# 0119-m328p.net
KiCad netlist of a schematic drawn in EAGLE
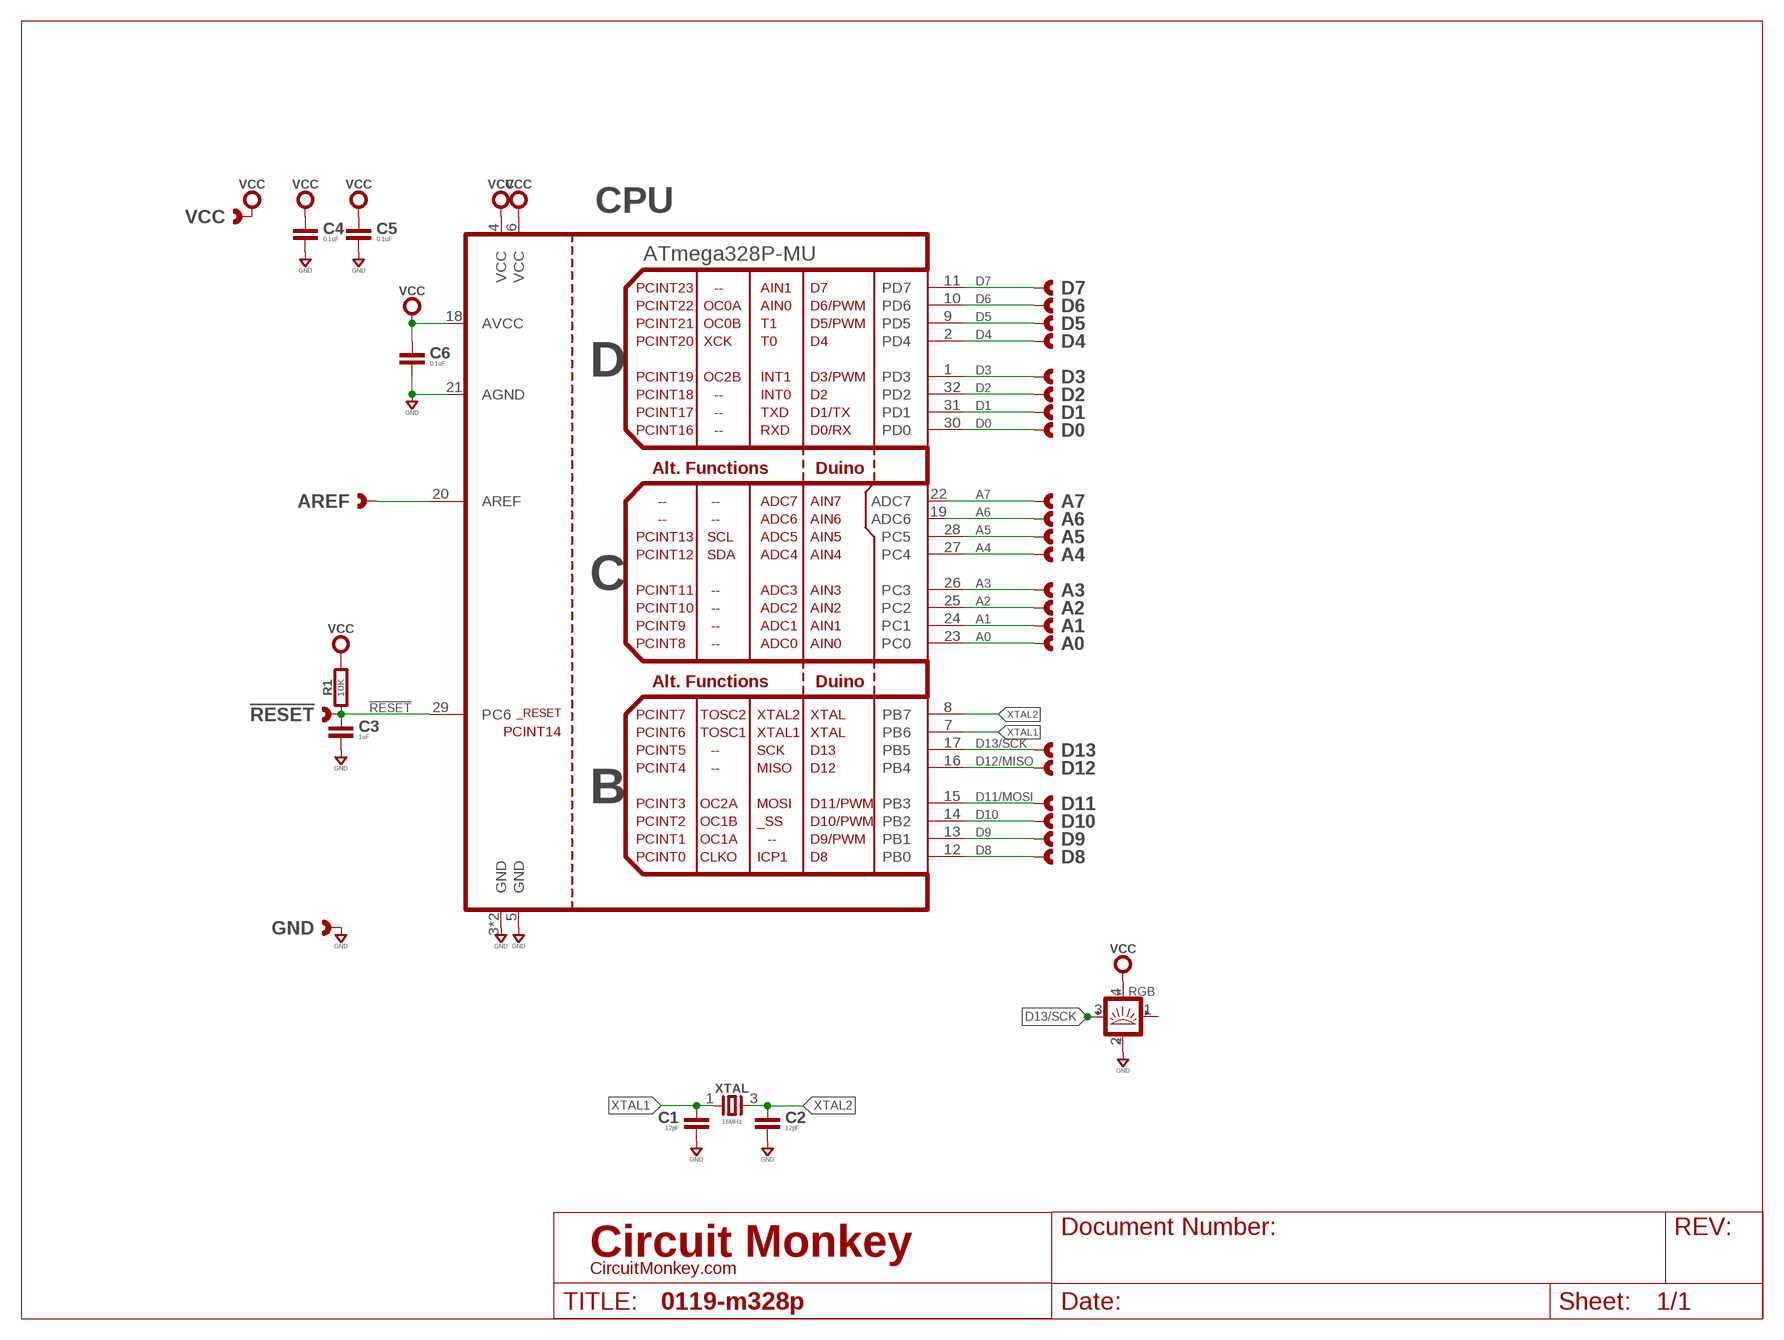
[diagram p0: schematic, sheet 1]

(export (version "E")
  (design (tool "Eeschema 10.0.6"))
  (components
    (comp (ref "!RESET")
      (value "CAST-01X12.00MM")
      (footprint "eagle-import:CAST01-2.00MM")
      (libsource (lib "eagle-import") (part "CAST-01X12.00MM"))
    )
    (comp (ref "A0")
      (value "CAST-01X12.00MM")
      (footprint "eagle-import:CAST01-2.00MM")
      (libsource (lib "eagle-import") (part "CAST-01X12.00MM"))
    )
    (comp (ref "A1")
      (value "CAST-01X12.00MM")
      (footprint "eagle-import:CAST01-2.00MM")
      (libsource (lib "eagle-import") (part "CAST-01X12.00MM"))
    )
    (comp (ref "A2")
      (value "CAST-01X12.00MM")
      (footprint "eagle-import:CAST01-2.00MM")
      (libsource (lib "eagle-import") (part "CAST-01X12.00MM"))
    )
    (comp (ref "A3")
      (value "CAST-01X12.00MM")
      (footprint "eagle-import:CAST01-2.00MM")
      (libsource (lib "eagle-import") (part "CAST-01X12.00MM"))
    )
    (comp (ref "A4")
      (value "CAST-01X12.00MM")
      (footprint "eagle-import:CAST01-2.00MM")
      (libsource (lib "eagle-import") (part "CAST-01X12.00MM"))
    )
    (comp (ref "A5")
      (value "CAST-01X12.00MM")
      (footprint "eagle-import:CAST01-2.00MM")
      (libsource (lib "eagle-import") (part "CAST-01X12.00MM"))
    )
    (comp (ref "A6")
      (value "CAST-01X12.00MM")
      (footprint "eagle-import:CAST01-2.00MM")
      (libsource (lib "eagle-import") (part "CAST-01X12.00MM"))
    )
    (comp (ref "A7")
      (value "CAST-01X12.00MM")
      (footprint "eagle-import:CAST01-2.00MM")
      (libsource (lib "eagle-import") (part "CAST-01X12.00MM"))
    )
    (comp (ref "AREF")
      (value "CAST-01X12.00MM")
      (footprint "eagle-import:CAST01-2.00MM")
      (libsource (lib "eagle-import") (part "CAST-01X12.00MM"))
    )
    (comp (ref "C1")
      (value "12pF")
      (footprint "eagle-import:0402-CAP")
      (libsource (lib "eagle-import") (part "CAPACITOR0402"))
    )
    (comp (ref "C2")
      (value "12pF")
      (footprint "eagle-import:0402-CAP")
      (libsource (lib "eagle-import") (part "CAPACITOR0402"))
    )
    (comp (ref "C3")
      (value "1uF")
      (footprint "eagle-import:0402-CAP")
      (libsource (lib "eagle-import") (part "CAPACITOR0402"))
    )
    (comp (ref "C4")
      (value "0.1uF")
      (footprint "eagle-import:0402-CAP")
      (libsource (lib "eagle-import") (part "CAPACITOR0402"))
    )
    (comp (ref "C5")
      (value "0.1uF")
      (footprint "eagle-import:0402-CAP")
      (libsource (lib "eagle-import") (part "CAPACITOR0402"))
    )
    (comp (ref "C6")
      (value "0.1uF")
      (footprint "eagle-import:0402-CAP")
      (libsource (lib "eagle-import") (part "CAPACITOR0402"))
    )
    (comp (ref "CPU")
      (value "ATmega328P-MU")
      (footprint "eagle-import:MLF32")
      (fields (field (name "MFR") "Atmel") (field (name "MPN") "atmega328p-mu"))
      (libsource (lib "eagle-import") (part "ATMEGA328MU"))
    )
    (comp (ref "D0")
      (value "CAST-01X12.00MM")
      (footprint "eagle-import:CAST01-2.00MM")
      (libsource (lib "eagle-import") (part "CAST-01X12.00MM"))
    )
    (comp (ref "D1")
      (value "CAST-01X12.00MM")
      (footprint "eagle-import:CAST01-2.00MM")
      (libsource (lib "eagle-import") (part "CAST-01X12.00MM"))
    )
    (comp (ref "D2")
      (value "CAST-01X12.00MM")
      (footprint "eagle-import:CAST01-2.00MM")
      (libsource (lib "eagle-import") (part "CAST-01X12.00MM"))
    )
    (comp (ref "D3")
      (value "CAST-01X12.00MM")
      (footprint "eagle-import:CAST01-2.00MM")
      (libsource (lib "eagle-import") (part "CAST-01X12.00MM"))
    )
    (comp (ref "D4")
      (value "CAST-01X12.00MM")
      (footprint "eagle-import:CAST01-2.00MM")
      (libsource (lib "eagle-import") (part "CAST-01X12.00MM"))
    )
    (comp (ref "D5")
      (value "CAST-01X12.00MM")
      (footprint "eagle-import:CAST01-2.00MM")
      (libsource (lib "eagle-import") (part "CAST-01X12.00MM"))
    )
    (comp (ref "D6")
      (value "CAST-01X12.00MM")
      (footprint "eagle-import:CAST01-2.00MM")
      (libsource (lib "eagle-import") (part "CAST-01X12.00MM"))
    )
    (comp (ref "D7")
      (value "CAST-01X12.00MM")
      (footprint "eagle-import:CAST01-2.00MM")
      (libsource (lib "eagle-import") (part "CAST-01X12.00MM"))
    )
    (comp (ref "D8")
      (value "CAST-01X12.00MM")
      (footprint "eagle-import:CAST01-2.00MM")
      (libsource (lib "eagle-import") (part "CAST-01X12.00MM"))
    )
    (comp (ref "D9")
      (value "CAST-01X12.00MM")
      (footprint "eagle-import:CAST01-2.00MM")
      (libsource (lib "eagle-import") (part "CAST-01X12.00MM"))
    )
    (comp (ref "D10")
      (value "CAST-01X12.00MM")
      (footprint "eagle-import:CAST01-2.00MM")
      (libsource (lib "eagle-import") (part "CAST-01X12.00MM"))
    )
    (comp (ref "D11")
      (value "CAST-01X12.00MM")
      (footprint "eagle-import:CAST01-2.00MM")
      (libsource (lib "eagle-import") (part "CAST-01X12.00MM"))
    )
    (comp (ref "D12")
      (value "CAST-01X12.00MM")
      (footprint "eagle-import:CAST01-2.00MM")
      (libsource (lib "eagle-import") (part "CAST-01X12.00MM"))
    )
    (comp (ref "D13")
      (value "CAST-01X12.00MM")
      (footprint "eagle-import:CAST01-2.00MM")
      (libsource (lib "eagle-import") (part "CAST-01X12.00MM"))
    )
    (comp (ref "GND")
      (value "CAST-01X12.00MM")
      (footprint "eagle-import:CAST01-2.00MM")
      (libsource (lib "eagle-import") (part "CAST-01X12.00MM"))
    )
    (comp (ref "R1")
      (value "10K")
      (footprint "eagle-import:0402-RES")
      (libsource (lib "eagle-import") (part "RESISTOR0402"))
    )
    (comp (ref "RGB")
      (value "SMART_LED2020")
      (footprint "eagle-import:SMD_2020")
      (libsource (lib "eagle-import") (part "SMART_LED2020"))
    )
    (comp (ref "VCC")
      (value "CAST-01X12.00MM")
      (footprint "eagle-import:CAST01-2.00MM")
      (libsource (lib "eagle-import") (part "CAST-01X12.00MM"))
    )
    (comp (ref "XTAL")
      (value "16MHz")
      (footprint "eagle-import:32X25")
      (fields (field (name "MF") "Epson") (field (name "MPN") "FA-238 16.0000MB-K3"))
      (libsource (lib "eagle-import") (part "2P3.2X2.5"))
    )
  )
  (nets
    (net (code "1") (name "/A0") (class "Default")
      (node (ref "A0") (pin "1") (pinfunction "1_1") (pintype "bidirectional"))
      (node (ref "A0") (pin "P$1") (pinfunction "1_P$1") (pintype "bidirectional"))
      (node (ref "A0") (pin "P$2") (pinfunction "1_P$2") (pintype "bidirectional"))
      (node (ref "CPU") (pin "23") (pinfunction "PC0_23") (pintype "bidirectional"))
    )
    (net (code "2") (name "/A1") (class "Default")
      (node (ref "A1") (pin "1") (pinfunction "1_1") (pintype "bidirectional"))
      (node (ref "A1") (pin "P$1") (pinfunction "1_P$1") (pintype "bidirectional"))
      (node (ref "A1") (pin "P$2") (pinfunction "1_P$2") (pintype "bidirectional"))
      (node (ref "CPU") (pin "24") (pinfunction "PC1_24") (pintype "bidirectional"))
    )
    (net (code "3") (name "/A2") (class "Default")
      (node (ref "A2") (pin "1") (pinfunction "1_1") (pintype "bidirectional"))
      (node (ref "A2") (pin "P$1") (pinfunction "1_P$1") (pintype "bidirectional"))
      (node (ref "A2") (pin "P$2") (pinfunction "1_P$2") (pintype "bidirectional"))
      (node (ref "CPU") (pin "25") (pinfunction "PC2_25") (pintype "bidirectional"))
    )
    (net (code "4") (name "/A3") (class "Default")
      (node (ref "A3") (pin "1") (pinfunction "1_1") (pintype "bidirectional"))
      (node (ref "A3") (pin "P$1") (pinfunction "1_P$1") (pintype "bidirectional"))
      (node (ref "A3") (pin "P$2") (pinfunction "1_P$2") (pintype "bidirectional"))
      (node (ref "CPU") (pin "26") (pinfunction "PC3_26") (pintype "bidirectional"))
    )
    (net (code "5") (name "/A4") (class "Default")
      (node (ref "A4") (pin "1") (pinfunction "1_1") (pintype "bidirectional"))
      (node (ref "A4") (pin "P$1") (pinfunction "1_P$1") (pintype "bidirectional"))
      (node (ref "A4") (pin "P$2") (pinfunction "1_P$2") (pintype "bidirectional"))
      (node (ref "CPU") (pin "27") (pinfunction "PC4_27") (pintype "bidirectional"))
    )
    (net (code "6") (name "/A5") (class "Default")
      (node (ref "A5") (pin "1") (pinfunction "1_1") (pintype "bidirectional"))
      (node (ref "A5") (pin "P$1") (pinfunction "1_P$1") (pintype "bidirectional"))
      (node (ref "A5") (pin "P$2") (pinfunction "1_P$2") (pintype "bidirectional"))
      (node (ref "CPU") (pin "28") (pinfunction "PC5_28") (pintype "bidirectional"))
    )
    (net (code "7") (name "/A6") (class "Default")
      (node (ref "A6") (pin "1") (pinfunction "1_1") (pintype "bidirectional"))
      (node (ref "A6") (pin "P$1") (pinfunction "1_P$1") (pintype "bidirectional"))
      (node (ref "A6") (pin "P$2") (pinfunction "1_P$2") (pintype "bidirectional"))
      (node (ref "CPU") (pin "19") (pinfunction "ADC6_19") (pintype "bidirectional"))
    )
    (net (code "8") (name "/A7") (class "Default")
      (node (ref "A7") (pin "1") (pinfunction "1_1") (pintype "bidirectional"))
      (node (ref "A7") (pin "P$1") (pinfunction "1_P$1") (pintype "bidirectional"))
      (node (ref "A7") (pin "P$2") (pinfunction "1_P$2") (pintype "bidirectional"))
      (node (ref "CPU") (pin "22") (pinfunction "ADC7_22") (pintype "bidirectional"))
    )
    (net (code "9") (name "/D0") (class "Default")
      (node (ref "CPU") (pin "30") (pinfunction "PD0_30") (pintype "bidirectional"))
      (node (ref "D0") (pin "1") (pinfunction "1_1") (pintype "bidirectional"))
      (node (ref "D0") (pin "P$1") (pinfunction "1_P$1") (pintype "bidirectional"))
      (node (ref "D0") (pin "P$2") (pinfunction "1_P$2") (pintype "bidirectional"))
    )
    (net (code "10") (name "/D1") (class "Default")
      (node (ref "CPU") (pin "31") (pinfunction "PD1_31") (pintype "bidirectional"))
      (node (ref "D1") (pin "1") (pinfunction "1_1") (pintype "bidirectional"))
      (node (ref "D1") (pin "P$1") (pinfunction "1_P$1") (pintype "bidirectional"))
      (node (ref "D1") (pin "P$2") (pinfunction "1_P$2") (pintype "bidirectional"))
    )
    (net (code "11") (name "/D2") (class "Default")
      (node (ref "CPU") (pin "32") (pinfunction "PD2_32") (pintype "bidirectional"))
      (node (ref "D2") (pin "1") (pinfunction "1_1") (pintype "bidirectional"))
      (node (ref "D2") (pin "P$1") (pinfunction "1_P$1") (pintype "bidirectional"))
      (node (ref "D2") (pin "P$2") (pinfunction "1_P$2") (pintype "bidirectional"))
    )
    (net (code "12") (name "/D3") (class "Default")
      (node (ref "CPU") (pin "1") (pinfunction "PD3_1") (pintype "bidirectional"))
      (node (ref "D3") (pin "1") (pinfunction "1_1") (pintype "bidirectional"))
      (node (ref "D3") (pin "P$1") (pinfunction "1_P$1") (pintype "bidirectional"))
      (node (ref "D3") (pin "P$2") (pinfunction "1_P$2") (pintype "bidirectional"))
    )
    (net (code "13") (name "/D4") (class "Default")
      (node (ref "CPU") (pin "2") (pinfunction "PD4_2") (pintype "bidirectional"))
      (node (ref "D4") (pin "1") (pinfunction "1_1") (pintype "bidirectional"))
      (node (ref "D4") (pin "P$1") (pinfunction "1_P$1") (pintype "bidirectional"))
      (node (ref "D4") (pin "P$2") (pinfunction "1_P$2") (pintype "bidirectional"))
    )
    (net (code "14") (name "/D5") (class "Default")
      (node (ref "CPU") (pin "9") (pinfunction "PD5_9") (pintype "bidirectional"))
      (node (ref "D5") (pin "1") (pinfunction "1_1") (pintype "bidirectional"))
      (node (ref "D5") (pin "P$1") (pinfunction "1_P$1") (pintype "bidirectional"))
      (node (ref "D5") (pin "P$2") (pinfunction "1_P$2") (pintype "bidirectional"))
    )
    (net (code "15") (name "/D6") (class "Default")
      (node (ref "CPU") (pin "10") (pinfunction "PD6_10") (pintype "bidirectional"))
      (node (ref "D6") (pin "1") (pinfunction "1_1") (pintype "bidirectional"))
      (node (ref "D6") (pin "P$1") (pinfunction "1_P$1") (pintype "bidirectional"))
      (node (ref "D6") (pin "P$2") (pinfunction "1_P$2") (pintype "bidirectional"))
    )
    (net (code "16") (name "/D7") (class "Default")
      (node (ref "CPU") (pin "11") (pinfunction "PD7_11") (pintype "bidirectional"))
      (node (ref "D7") (pin "1") (pinfunction "1_1") (pintype "bidirectional"))
      (node (ref "D7") (pin "P$1") (pinfunction "1_P$1") (pintype "bidirectional"))
      (node (ref "D7") (pin "P$2") (pinfunction "1_P$2") (pintype "bidirectional"))
    )
    (net (code "17") (name "/D8") (class "Default")
      (node (ref "CPU") (pin "12") (pinfunction "PB0_12") (pintype "bidirectional"))
      (node (ref "D8") (pin "1") (pinfunction "1_1") (pintype "bidirectional"))
      (node (ref "D8") (pin "P$1") (pinfunction "1_P$1") (pintype "bidirectional"))
      (node (ref "D8") (pin "P$2") (pinfunction "1_P$2") (pintype "bidirectional"))
    )
    (net (code "18") (name "/D9") (class "Default")
      (node (ref "CPU") (pin "13") (pinfunction "PB1_13") (pintype "bidirectional"))
      (node (ref "D9") (pin "1") (pinfunction "1_1") (pintype "bidirectional"))
      (node (ref "D9") (pin "P$1") (pinfunction "1_P$1") (pintype "bidirectional"))
      (node (ref "D9") (pin "P$2") (pinfunction "1_P$2") (pintype "bidirectional"))
    )
    (net (code "19") (name "/D10") (class "Default")
      (node (ref "CPU") (pin "14") (pinfunction "PB2_14") (pintype "bidirectional"))
      (node (ref "D10") (pin "1") (pinfunction "1_1") (pintype "bidirectional"))
      (node (ref "D10") (pin "P$1") (pinfunction "1_P$1") (pintype "bidirectional"))
      (node (ref "D10") (pin "P$2") (pinfunction "1_P$2") (pintype "bidirectional"))
    )
    (net (code "20") (name "/D11{slash}MOSI") (class "Default")
      (node (ref "CPU") (pin "15") (pinfunction "PB3_15") (pintype "bidirectional"))
      (node (ref "D11") (pin "1") (pinfunction "1_1") (pintype "bidirectional"))
      (node (ref "D11") (pin "P$1") (pinfunction "1_P$1") (pintype "bidirectional"))
      (node (ref "D11") (pin "P$2") (pinfunction "1_P$2") (pintype "bidirectional"))
    )
    (net (code "21") (name "/D12{slash}MISO") (class "Default")
      (node (ref "CPU") (pin "16") (pinfunction "PB4_16") (pintype "bidirectional"))
      (node (ref "D12") (pin "1") (pinfunction "1_1") (pintype "bidirectional"))
      (node (ref "D12") (pin "P$1") (pinfunction "1_P$1") (pintype "bidirectional"))
      (node (ref "D12") (pin "P$2") (pinfunction "1_P$2") (pintype "bidirectional"))
    )
    (net (code "22") (name "/~{RESET}") (class "Default")
      (node (ref "!RESET") (pin "1") (pinfunction "1_1") (pintype "bidirectional"))
      (node (ref "!RESET") (pin "P$1") (pinfunction "1_P$1") (pintype "bidirectional"))
      (node (ref "!RESET") (pin "P$2") (pinfunction "1_P$2") (pintype "bidirectional"))
      (node (ref "C3") (pin "1") (pinfunction "1_1") (pintype "passive"))
      (node (ref "CPU") (pin "29") (pinfunction "PC6_29") (pintype "bidirectional"))
      (node (ref "R1") (pin "1") (pinfunction "1_1") (pintype "passive"))
    )
    (net (code "23") (name "D13{slash}SCK") (class "Default")
      (node (ref "CPU") (pin "17") (pinfunction "PB5_17") (pintype "bidirectional"))
      (node (ref "D13") (pin "1") (pinfunction "1_1") (pintype "bidirectional"))
      (node (ref "D13") (pin "P$1") (pinfunction "1_P$1") (pintype "bidirectional"))
      (node (ref "D13") (pin "P$2") (pinfunction "1_P$2") (pintype "bidirectional"))
      (node (ref "RGB") (pin "3") (pinfunction "IN_3") (pintype "bidirectional"))
    )
    (net (code "24") (name "GND") (class "Default")
      (node (ref "C1") (pin "2") (pinfunction "2_2") (pintype "passive"))
      (node (ref "C2") (pin "2") (pinfunction "2_2") (pintype "passive"))
      (node (ref "C3") (pin "2") (pinfunction "2_2") (pintype "passive"))
      (node (ref "C4") (pin "2") (pinfunction "2_2") (pintype "passive"))
      (node (ref "C5") (pin "2") (pinfunction "2_2") (pintype "passive"))
      (node (ref "C6") (pin "2") (pinfunction "2_2") (pintype "passive"))
      (node (ref "CPU") (pin "21") (pinfunction "AGND_21") (pintype "power_in"))
      (node (ref "CPU") (pin "3") (pinfunction "GND_3") (pintype "power_in"))
      (node (ref "CPU") (pin "5") (pinfunction "GND_5") (pintype "power_in"))
      (node (ref "CPU") (pin "PAD") (pinfunction "GND_PAD") (pintype "power_in"))
      (node (ref "GND") (pin "1") (pinfunction "1_1") (pintype "bidirectional"))
      (node (ref "GND") (pin "P$1") (pinfunction "1_P$1") (pintype "bidirectional"))
      (node (ref "GND") (pin "P$2") (pinfunction "1_P$2") (pintype "bidirectional"))
      (node (ref "RGB") (pin "2") (pinfunction "GND_2") (pintype "bidirectional"))
    )
    (net (code "25") (name "Net-(CPU-AREF)") (class "Default")
      (node (ref "AREF") (pin "1") (pinfunction "1_1") (pintype "bidirectional"))
      (node (ref "AREF") (pin "P$1") (pinfunction "1_P$1") (pintype "bidirectional"))
      (node (ref "AREF") (pin "P$2") (pinfunction "1_P$2") (pintype "bidirectional"))
      (node (ref "CPU") (pin "20") (pinfunction "AREF_20") (pintype "input"))
    )
    (net (code "26") (name "VCC") (class "Default")
      (node (ref "C4") (pin "1") (pinfunction "1_1") (pintype "passive"))
      (node (ref "C5") (pin "1") (pinfunction "1_1") (pintype "passive"))
      (node (ref "C6") (pin "1") (pinfunction "1_1") (pintype "passive"))
      (node (ref "CPU") (pin "18") (pinfunction "AVCC_18") (pintype "power_in"))
      (node (ref "CPU") (pin "4") (pinfunction "VCC_4") (pintype "power_in"))
      (node (ref "CPU") (pin "6") (pinfunction "VCC_6") (pintype "power_in"))
      (node (ref "R1") (pin "2") (pinfunction "2_2") (pintype "passive"))
      (node (ref "RGB") (pin "4") (pinfunction "VDD_4") (pintype "bidirectional"))
      (node (ref "VCC") (pin "1") (pinfunction "1_1") (pintype "bidirectional"))
      (node (ref "VCC") (pin "P$1") (pinfunction "1_P$1") (pintype "bidirectional"))
      (node (ref "VCC") (pin "P$2") (pinfunction "1_P$2") (pintype "bidirectional"))
    )
    (net (code "27") (name "XTAL1") (class "Default")
      (node (ref "C1") (pin "1") (pinfunction "1_1") (pintype "passive"))
      (node (ref "CPU") (pin "7") (pinfunction "PB6_7") (pintype "bidirectional"))
      (node (ref "XTAL") (pin "1") (pinfunction "P$1_1") (pintype "passive"))
    )
    (net (code "28") (name "XTAL2") (class "Default")
      (node (ref "C2") (pin "1") (pinfunction "1_1") (pintype "passive"))
      (node (ref "CPU") (pin "8") (pinfunction "PB7_8") (pintype "bidirectional"))
      (node (ref "XTAL") (pin "3") (pinfunction "P$2_3") (pintype "passive"))
    )
    (net (code "29") (name "unconnected-(RGB-OUT-Pad1)") (class "Default")
      (node (ref "RGB") (pin "1") (pinfunction "OUT_1") (pintype "bidirectional"))
    )
  )
)
